# EsquematicoAudio.net
KiCad netlist of a schematic drawn in Altium Designer
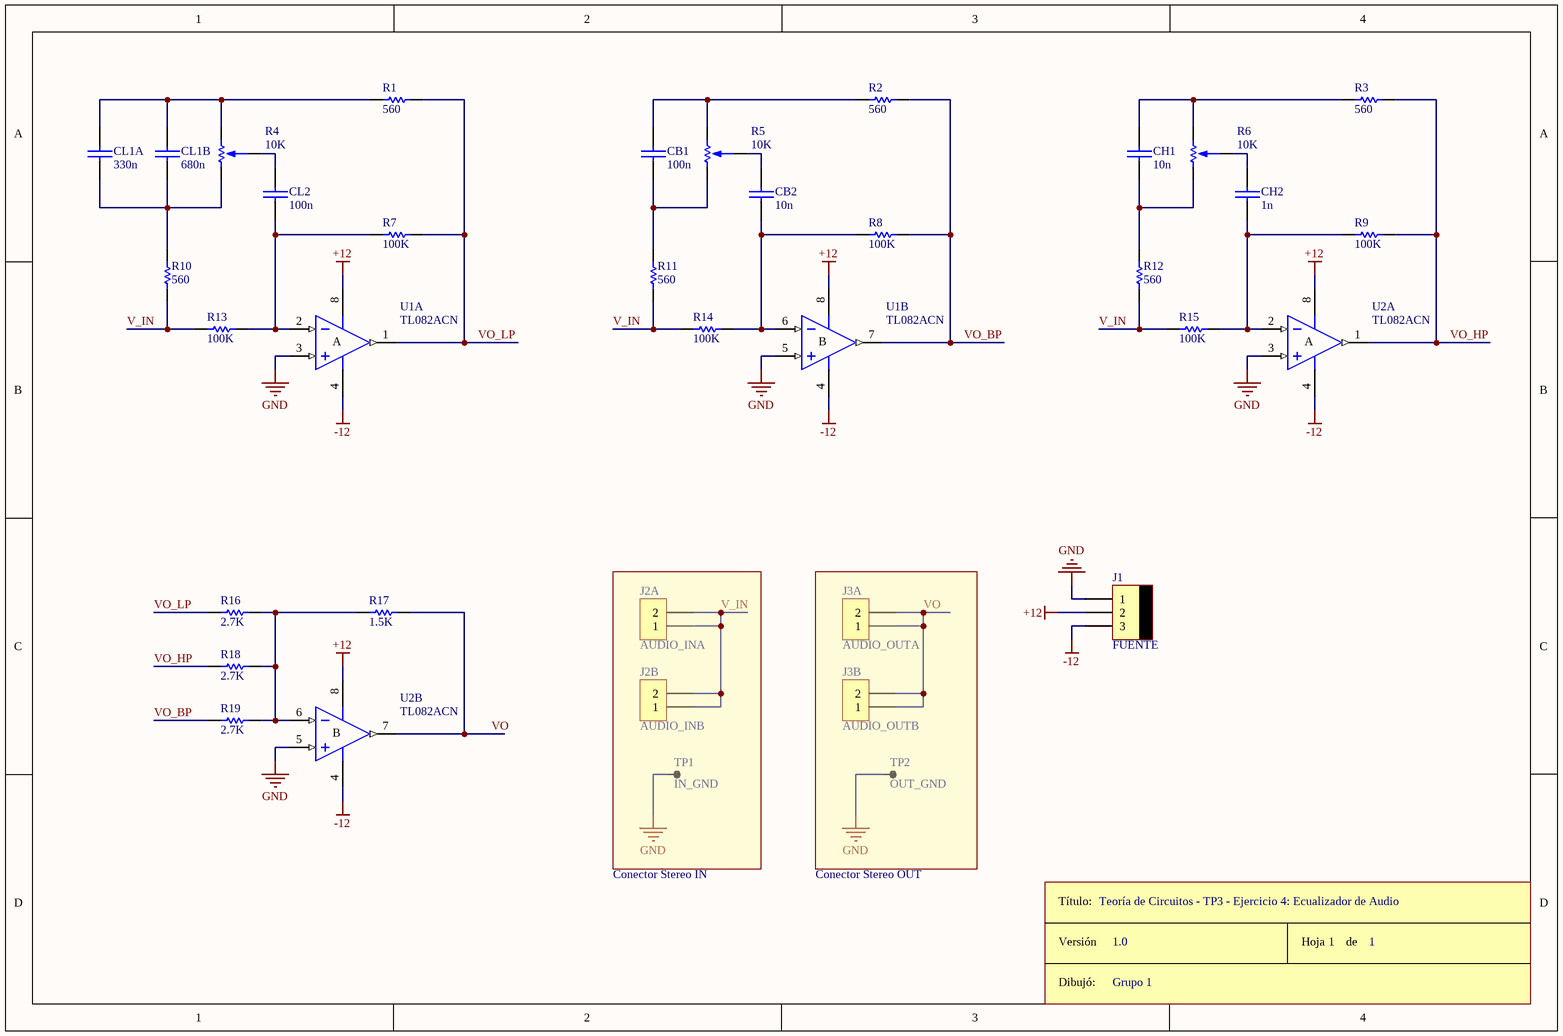
[diagram p0: EsquematicoAudio.SchDoc]

(export (version "E")
  (design (tool "Eeschema 10.0.6"))
  (components
    (comp (ref "1") (value "Rótulo") (libsource (lib "LIB PIO IX") (part "Rótulo")))
    (comp (ref "CB1") (value "100n") (footprint "CAP100") (libsource (lib "LIBEBAL") (part "CAP")))
    (comp (ref "CB2") (value "10n") (footprint "CAP200") (libsource (lib "LIBEBAL") (part "CAP")))
    (comp (ref "CH1") (value "10n") (footprint "CAP200") (libsource (lib "LIBEBAL") (part "CAP")))
    (comp (ref "CH2") (value "1n") (footprint "CAP100") (libsource (lib "LIBEBAL") (part "CAP")))
    (comp (ref "CL1A") (value "330n") (footprint "CAP100") (libsource (lib "LIBEBAL") (part "CAP")))
    (comp (ref "CL1B") (value "680n") (footprint "CAP100") (libsource (lib "LIBEBAL") (part "CAP")))
    (comp (ref "CL2") (value "100n") (footprint "CAP100") (libsource (lib "LIBEBAL") (part "CAP")))
    (comp (ref "J1") (value "FUENTE") (footprint "MOLEX3") (libsource (lib "LIBEBAL") (part "MOLEX3")))
    (comp (ref "J2A") (value "AUDIO_INA") (footprint "SIP2") (libsource (lib "LIBEBAL") (part "CON2")))
    (comp (ref "J2B") (value "AUDIO_INB") (footprint "SIP2") (libsource (lib "LIBEBAL") (part "CON2")))
    (comp (ref "J3A") (value "AUDIO_OUTA") (footprint "SIP2") (libsource (lib "LIBEBAL") (part "CON2")))
    (comp (ref "J3B") (value "AUDIO_OUTB") (footprint "SIP2") (libsource (lib "LIBEBAL") (part "CON2")))
    (comp (ref "R1") (value "560") (footprint "RES300") (libsource (lib "LIBEBAL") (part "RES")))
    (comp (ref "R2") (value "560") (footprint "RES300") (libsource (lib "LIBEBAL") (part "RES")))
    (comp (ref "R3") (value "560") (footprint "RES300") (libsource (lib "LIBEBAL") (part "RES")))
    (comp (ref "R4")
      (value "10K")
      (footprint "POTENCIOMETRO")
      (libsource (lib "LIBEBAL") (part "POTENCIOMETRO"))
    )
    (comp (ref "R5")
      (value "10K")
      (footprint "POTENCIOMETRO")
      (libsource (lib "LIBEBAL") (part "POTENCIOMETRO"))
    )
    (comp (ref "R6")
      (value "10K")
      (footprint "POTENCIOMETRO")
      (libsource (lib "LIBEBAL") (part "POTENCIOMETRO"))
    )
    (comp (ref "R7") (value "100K") (footprint "RES300") (libsource (lib "LIBEBAL") (part "RES")))
    (comp (ref "R8") (value "100K") (footprint "RES300") (libsource (lib "LIBEBAL") (part "RES")))
    (comp (ref "R9") (value "100K") (footprint "RES300") (libsource (lib "LIBEBAL") (part "RES")))
    (comp (ref "R10") (value "560") (footprint "RES300") (libsource (lib "LIBEBAL") (part "RES")))
    (comp (ref "R11") (value "560") (footprint "RES300") (libsource (lib "LIBEBAL") (part "RES")))
    (comp (ref "R12") (value "560") (footprint "RES300") (libsource (lib "LIBEBAL") (part "RES")))
    (comp (ref "R13") (value "100K") (footprint "RES300") (libsource (lib "LIBEBAL") (part "RES")))
    (comp (ref "R14") (value "100K") (footprint "RES300") (libsource (lib "LIBEBAL") (part "RES")))
    (comp (ref "R15") (value "100K") (footprint "RES300") (libsource (lib "LIBEBAL") (part "RES")))
    (comp (ref "R16") (value "2.7K") (footprint "RES300") (libsource (lib "LIBEBAL") (part "RES")))
    (comp (ref "R17") (value "1.5K") (footprint "RES300") (libsource (lib "LIBEBAL") (part "RES")))
    (comp (ref "R18") (value "2.7K") (footprint "RES300") (libsource (lib "LIBEBAL") (part "RES")))
    (comp (ref "R19") (value "2.7K") (footprint "RES300") (libsource (lib "LIBEBAL") (part "RES")))
    (comp (ref "TP1") (value "IN_GND") (footprint "TPTH") (libsource (lib "LIBEBAL") (part "TP")))
    (comp (ref "TP2") (value "OUT_GND") (footprint "TPTH") (libsource (lib "LIBEBAL") (part "TP")))
    (comp (ref "U1")
      (value "TL082ACN")
      (footprint "DIP8")
      (description "General-Purpose J-FET Dual Operational Amplifier")
      (fields (field (name "PUBLISHER") "Altium Limited"))
      (libsource (lib "ST Operational Amplifier") (part "TL082ACN"))
    )
    (comp (ref "U2")
      (value "TL082ACN")
      (footprint "DIP8")
      (description "General-Purpose J-FET Dual Operational Amplifier")
      (fields (field (name "PUBLISHER") "Altium Limited"))
      (libsource (lib "ST Operational Amplifier") (part "TL082ACN"))
    )
  )
  (nets
    (net (code "1") (name "+12") (class "Default")
      (node (ref "J1") (pin "2") (pinfunction "2_2") (pintype "passive"))
      (node (ref "U1") (pin "8") (pinfunction "V+_8") (pintype "power_in"))
      (node (ref "U2") (pin "8") (pinfunction "V+_8") (pintype "power_in"))
    )
    (net (code "2") (name "-12") (class "Default")
      (node (ref "J1") (pin "3") (pinfunction "3_3") (pintype "passive"))
      (node (ref "U1") (pin "4") (pinfunction "V-_4") (pintype "power_in"))
      (node (ref "U2") (pin "4") (pinfunction "V-_4") (pintype "power_in"))
    )
    (net (code "3") (name "/VO") (class "Default")
      (node (ref "J3A") (pin "1") (pinfunction "1_1") (pintype "passive"))
      (node (ref "J3A") (pin "2") (pinfunction "2_2") (pintype "passive"))
      (node (ref "J3B") (pin "1") (pinfunction "1_1") (pintype "passive"))
      (node (ref "J3B") (pin "2") (pinfunction "2_2") (pintype "passive"))
      (node (ref "R17") (pin "2") (pinfunction "2_2") (pintype "passive"))
      (node (ref "U2") (pin "7") (pinfunction "OUT_7") (pintype "output"))
    )
    (net (code "4") (name "/VO_BP") (class "Default")
      (node (ref "R19") (pin "1") (pinfunction "1_1") (pintype "passive"))
      (node (ref "R2") (pin "2") (pinfunction "2_2") (pintype "passive"))
      (node (ref "R8") (pin "2") (pinfunction "2_2") (pintype "passive"))
      (node (ref "U1") (pin "7") (pinfunction "OUT_7") (pintype "output"))
    )
    (net (code "5") (name "/VO_HP") (class "Default")
      (node (ref "R18") (pin "1") (pinfunction "1_1") (pintype "passive"))
      (node (ref "R3") (pin "2") (pinfunction "2_2") (pintype "passive"))
      (node (ref "R9") (pin "2") (pinfunction "2_2") (pintype "passive"))
      (node (ref "U2") (pin "1") (pinfunction "OUT_1") (pintype "output"))
    )
    (net (code "6") (name "/VO_LP") (class "Default")
      (node (ref "R1") (pin "2") (pinfunction "2_2") (pintype "passive"))
      (node (ref "R16") (pin "1") (pinfunction "1_1") (pintype "passive"))
      (node (ref "R7") (pin "2") (pinfunction "2_2") (pintype "passive"))
      (node (ref "U1") (pin "1") (pinfunction "OUT_1") (pintype "output"))
    )
    (net (code "7") (name "/V_IN") (class "Default")
      (node (ref "J2A") (pin "1") (pinfunction "1_1") (pintype "passive"))
      (node (ref "J2A") (pin "2") (pinfunction "2_2") (pintype "passive"))
      (node (ref "J2B") (pin "1") (pinfunction "1_1") (pintype "passive"))
      (node (ref "J2B") (pin "2") (pinfunction "2_2") (pintype "passive"))
      (node (ref "R10") (pin "1") (pinfunction "1_1") (pintype "passive"))
      (node (ref "R11") (pin "1") (pinfunction "1_1") (pintype "passive"))
      (node (ref "R12") (pin "1") (pinfunction "1_1") (pintype "passive"))
      (node (ref "R13") (pin "1") (pinfunction "1_1") (pintype "passive"))
      (node (ref "R14") (pin "1") (pinfunction "1_1") (pintype "passive"))
      (node (ref "R15") (pin "1") (pinfunction "1_1") (pintype "passive"))
    )
    (net (code "8") (name "GND") (class "Default")
      (node (ref "J1") (pin "1") (pinfunction "1_1") (pintype "passive"))
      (node (ref "TP1") (pin "1") (pinfunction "1_1") (pintype "passive"))
      (node (ref "TP2") (pin "1") (pinfunction "1_1") (pintype "passive"))
      (node (ref "U1") (pin "3") (pinfunction "IN+_3") (pintype "input"))
      (node (ref "U1") (pin "5") (pinfunction "IN+_5") (pintype "input"))
      (node (ref "U2") (pin "3") (pinfunction "IN+_3") (pintype "input"))
      (node (ref "U2") (pin "5") (pinfunction "IN+_5") (pintype "input"))
    )
    (net (code "9") (name "Net-(CB1-Pad1)") (class "Default")
      (node (ref "CB1") (pin "1") (pinfunction "1_1") (pintype "passive"))
      (node (ref "R2") (pin "1") (pinfunction "1_1") (pintype "passive"))
      (node (ref "R5") (pin "1") (pinfunction "1_1") (pintype "passive"))
    )
    (net (code "10") (name "Net-(CB1-Pad2)") (class "Default")
      (node (ref "CB1") (pin "2") (pinfunction "2_2") (pintype "passive"))
      (node (ref "R11") (pin "2") (pinfunction "2_2") (pintype "passive"))
      (node (ref "R5") (pin "3") (pinfunction "3_3") (pintype "passive"))
    )
    (net (code "11") (name "Net-(CB2-Pad1)") (class "Default")
      (node (ref "CB2") (pin "1") (pinfunction "1_1") (pintype "passive"))
      (node (ref "R5") (pin "2") (pinfunction "2_2") (pintype "passive"))
    )
    (net (code "12") (name "Net-(CH1-Pad1)") (class "Default")
      (node (ref "CH1") (pin "1") (pinfunction "1_1") (pintype "passive"))
      (node (ref "R3") (pin "1") (pinfunction "1_1") (pintype "passive"))
      (node (ref "R6") (pin "1") (pinfunction "1_1") (pintype "passive"))
    )
    (net (code "13") (name "Net-(CH1-Pad2)") (class "Default")
      (node (ref "CH1") (pin "2") (pinfunction "2_2") (pintype "passive"))
      (node (ref "R12") (pin "2") (pinfunction "2_2") (pintype "passive"))
      (node (ref "R6") (pin "3") (pinfunction "3_3") (pintype "passive"))
    )
    (net (code "14") (name "Net-(CH2-Pad1)") (class "Default")
      (node (ref "CH2") (pin "1") (pinfunction "1_1") (pintype "passive"))
      (node (ref "R6") (pin "2") (pinfunction "2_2") (pintype "passive"))
    )
    (net (code "15") (name "Net-(CL1A-Pad1)") (class "Default")
      (node (ref "CL1A") (pin "1") (pinfunction "1_1") (pintype "passive"))
      (node (ref "CL1B") (pin "2") (pinfunction "2_2") (pintype "passive"))
      (node (ref "R1") (pin "1") (pinfunction "1_1") (pintype "passive"))
      (node (ref "R4") (pin "1") (pinfunction "1_1") (pintype "passive"))
    )
    (net (code "16") (name "Net-(CL1A-Pad2)") (class "Default")
      (node (ref "CL1A") (pin "2") (pinfunction "2_2") (pintype "passive"))
      (node (ref "CL1B") (pin "1") (pinfunction "1_1") (pintype "passive"))
      (node (ref "R10") (pin "2") (pinfunction "2_2") (pintype "passive"))
      (node (ref "R4") (pin "3") (pinfunction "3_3") (pintype "passive"))
    )
    (net (code "17") (name "Net-(CL2-Pad1)") (class "Default")
      (node (ref "CL2") (pin "1") (pinfunction "1_1") (pintype "passive"))
      (node (ref "R4") (pin "2") (pinfunction "2_2") (pintype "passive"))
    )
    (net (code "18") (name "Net-(U1A-IN-)") (class "Default")
      (node (ref "CL2") (pin "2") (pinfunction "2_2") (pintype "passive"))
      (node (ref "R13") (pin "2") (pinfunction "2_2") (pintype "passive"))
      (node (ref "R7") (pin "1") (pinfunction "1_1") (pintype "passive"))
      (node (ref "U1") (pin "2") (pinfunction "IN-_2") (pintype "input"))
    )
    (net (code "19") (name "Net-(U1B-IN-)") (class "Default")
      (node (ref "CB2") (pin "2") (pinfunction "2_2") (pintype "passive"))
      (node (ref "R14") (pin "2") (pinfunction "2_2") (pintype "passive"))
      (node (ref "R8") (pin "1") (pinfunction "1_1") (pintype "passive"))
      (node (ref "U1") (pin "6") (pinfunction "IN-_6") (pintype "input"))
    )
    (net (code "20") (name "Net-(U2A-IN-)") (class "Default")
      (node (ref "CH2") (pin "2") (pinfunction "2_2") (pintype "passive"))
      (node (ref "R15") (pin "2") (pinfunction "2_2") (pintype "passive"))
      (node (ref "R9") (pin "1") (pinfunction "1_1") (pintype "passive"))
      (node (ref "U2") (pin "2") (pinfunction "IN-_2") (pintype "input"))
    )
    (net (code "21") (name "Net-(U2B-IN-)") (class "Default")
      (node (ref "R16") (pin "2") (pinfunction "2_2") (pintype "passive"))
      (node (ref "R17") (pin "1") (pinfunction "1_1") (pintype "passive"))
      (node (ref "R18") (pin "2") (pinfunction "2_2") (pintype "passive"))
      (node (ref "R19") (pin "2") (pinfunction "2_2") (pintype "passive"))
      (node (ref "U2") (pin "6") (pinfunction "IN-_6") (pintype "input"))
    )
  )
)
